# IR_Controller_v2.net
KiCad netlist of a schematic drawn in EAGLE
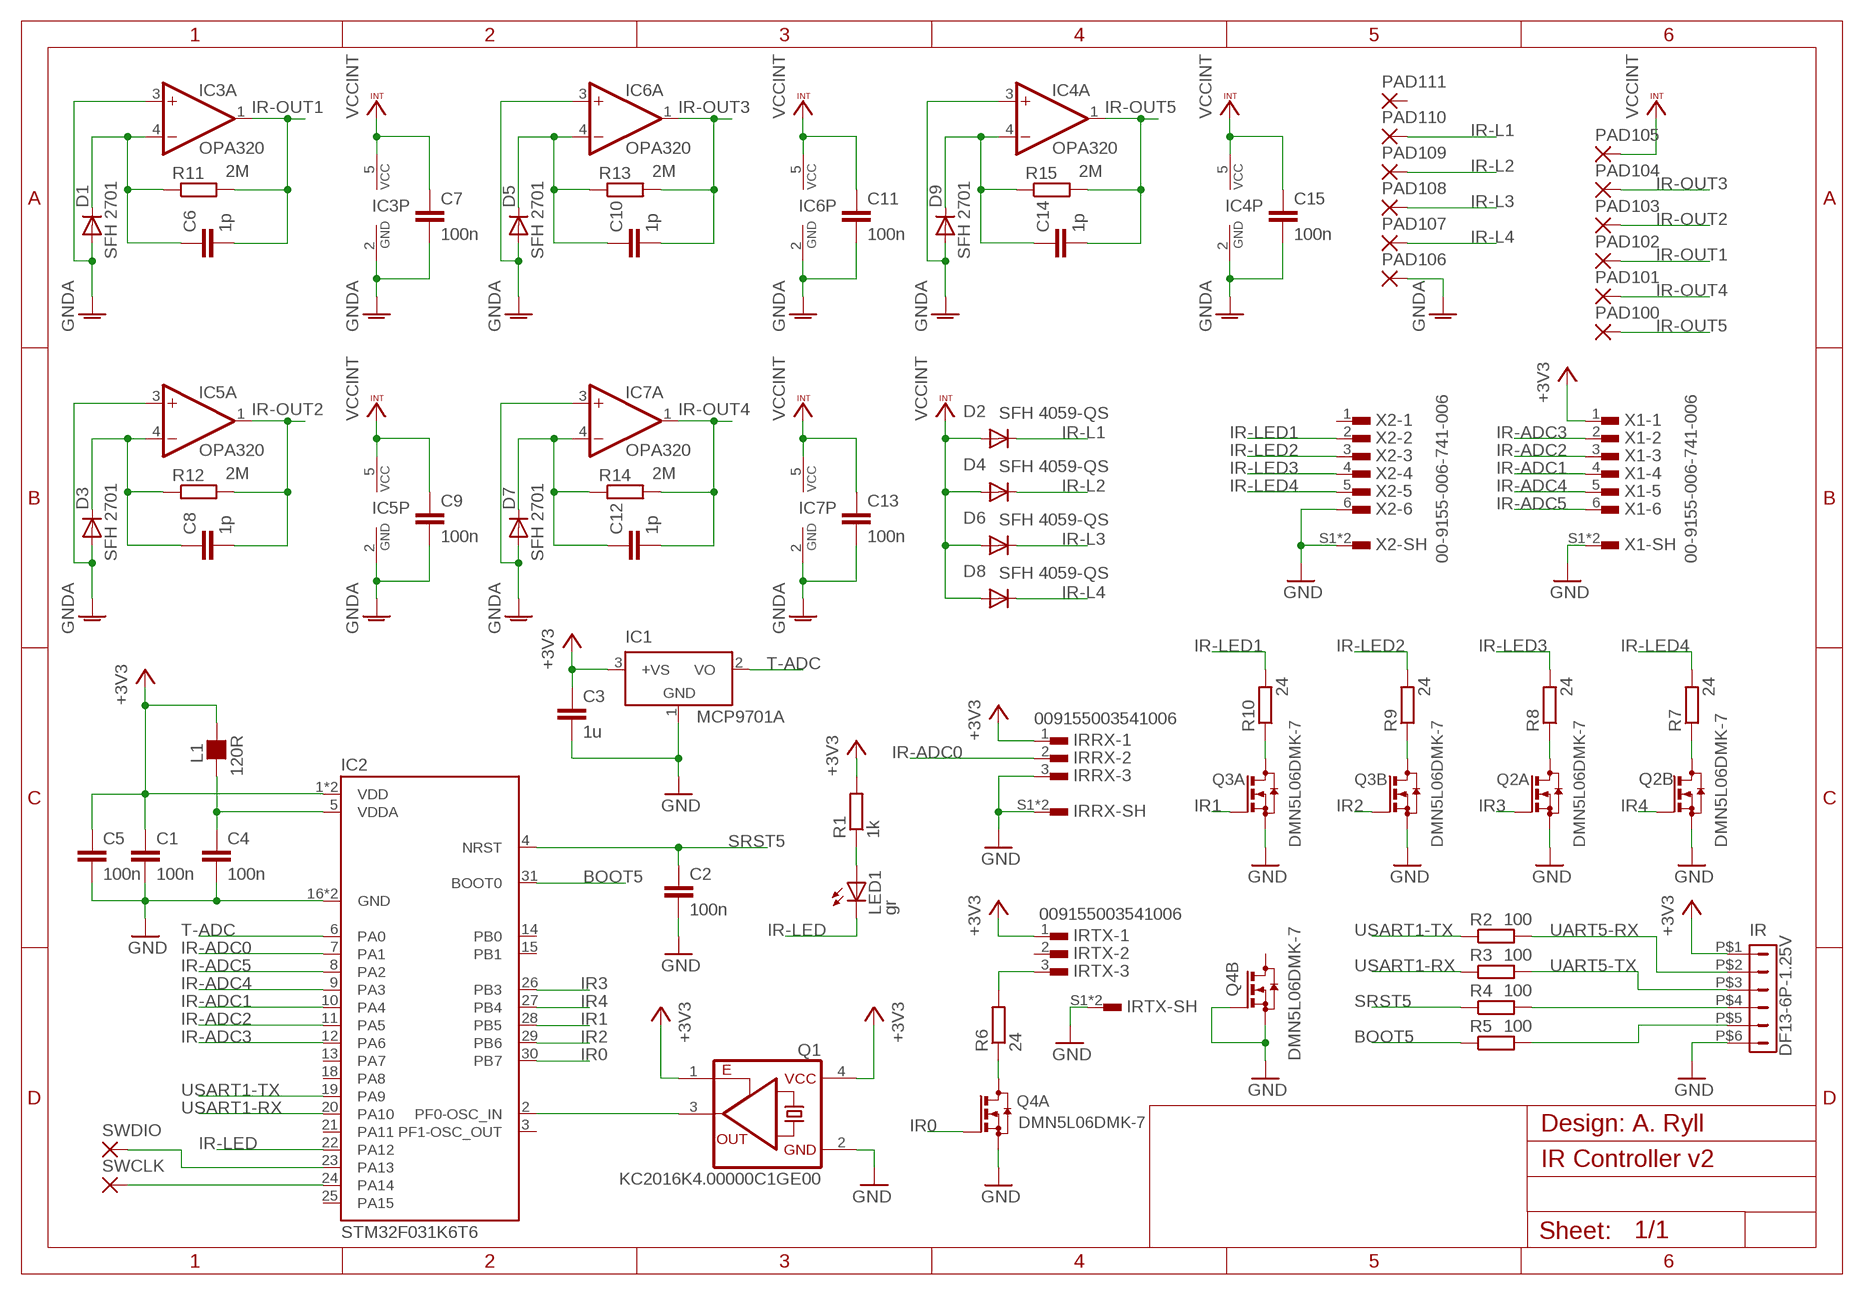
[diagram p0: schematic, sheet 1]

(export (version "E")
  (design (tool "Eeschema 10.0.6"))
  (components
    (comp (ref "C1")
      (value "100n")
      (footprint "eagle-import:C0603")
      (libsource (lib "eagle-import") (part "C-EUC0603"))
    )
    (comp (ref "C2")
      (value "100n")
      (footprint "eagle-import:C0603")
      (libsource (lib "eagle-import") (part "C-EUC0603"))
    )
    (comp (ref "C3")
      (value "1u")
      (footprint "eagle-import:C0603")
      (libsource (lib "eagle-import") (part "C-EUC0603"))
    )
    (comp (ref "C4")
      (value "100n")
      (footprint "eagle-import:C0603")
      (libsource (lib "eagle-import") (part "C-EUC0603"))
    )
    (comp (ref "C5")
      (value "100n")
      (footprint "eagle-import:C0603")
      (libsource (lib "eagle-import") (part "C-EUC0603"))
    )
    (comp (ref "C6")
      (value "1p")
      (footprint "eagle-import:C0603")
      (libsource (lib "eagle-import") (part "C-EUC0603"))
    )
    (comp (ref "C7")
      (value "100n")
      (footprint "eagle-import:C0603")
      (libsource (lib "eagle-import") (part "C-EUC0603"))
    )
    (comp (ref "C8")
      (value "1p")
      (footprint "eagle-import:C0603")
      (libsource (lib "eagle-import") (part "C-EUC0603"))
    )
    (comp (ref "C9")
      (value "100n")
      (footprint "eagle-import:C0603")
      (libsource (lib "eagle-import") (part "C-EUC0603"))
    )
    (comp (ref "C10")
      (value "1p")
      (footprint "eagle-import:C0603")
      (libsource (lib "eagle-import") (part "C-EUC0603"))
    )
    (comp (ref "C11")
      (value "100n")
      (footprint "eagle-import:C0603")
      (libsource (lib "eagle-import") (part "C-EUC0603"))
    )
    (comp (ref "C12")
      (value "1p")
      (footprint "eagle-import:C0603")
      (libsource (lib "eagle-import") (part "C-EUC0603"))
    )
    (comp (ref "C13")
      (value "100n")
      (footprint "eagle-import:C0603")
      (libsource (lib "eagle-import") (part "C-EUC0603"))
    )
    (comp (ref "C14")
      (value "1p")
      (footprint "eagle-import:C0603")
      (libsource (lib "eagle-import") (part "C-EUC0603"))
    )
    (comp (ref "C15")
      (value "100n")
      (footprint "eagle-import:C0603")
      (libsource (lib "eagle-import") (part "C-EUC0603"))
    )
    (comp (ref "D1")
      (value "SFH 2701")
      (footprint "eagle-import:LED-GULL")
      (libsource (lib "eagle-import") (part "DIODEG"))
    )
    (comp (ref "D2")
      (value "SFH 4059-QS")
      (footprint "eagle-import:LED-GULL")
      (libsource (lib "eagle-import") (part "DIODEG"))
    )
    (comp (ref "D3")
      (value "SFH 2701")
      (footprint "eagle-import:LED-GULL")
      (libsource (lib "eagle-import") (part "DIODEG"))
    )
    (comp (ref "D4")
      (value "SFH 4059-QS")
      (footprint "eagle-import:LED-GULL")
      (libsource (lib "eagle-import") (part "DIODEG"))
    )
    (comp (ref "D5")
      (value "SFH 2701")
      (footprint "eagle-import:LED-GULL")
      (libsource (lib "eagle-import") (part "DIODEG"))
    )
    (comp (ref "D6")
      (value "SFH 4059-QS")
      (footprint "eagle-import:LED-GULL")
      (libsource (lib "eagle-import") (part "DIODEG"))
    )
    (comp (ref "D7")
      (value "SFH 2701")
      (footprint "eagle-import:LED-GULL")
      (libsource (lib "eagle-import") (part "DIODEG"))
    )
    (comp (ref "D8")
      (value "SFH 4059-QS")
      (footprint "eagle-import:LED-GULL")
      (libsource (lib "eagle-import") (part "DIODEG"))
    )
    (comp (ref "D9")
      (value "SFH 2701")
      (footprint "eagle-import:LED-GULL")
      (libsource (lib "eagle-import") (part "DIODEG"))
    )
    (comp (ref "IC1")
      (value "MCP9701A")
      (footprint "eagle-import:TO92")
      (libsource (lib "eagle-import") (part "LM60P"))
    )
    (comp (ref "IC2")
      (value "STM32F031K6T6")
      (footprint "eagle-import:LQFP32-ST")
      (libsource (lib "eagle-import") (part "STM32F031K_TT"))
    )
    (comp (ref "IC3")
      (value "OPA320")
      (footprint "eagle-import:SOT23-5")
      (libsource (lib "eagle-import") (part "AD-OP1RT"))
    )
    (comp (ref "IC4")
      (value "OPA320")
      (footprint "eagle-import:SOT23-5")
      (libsource (lib "eagle-import") (part "AD-OP1RT"))
    )
    (comp (ref "IC5")
      (value "OPA320")
      (footprint "eagle-import:SOT23-5")
      (libsource (lib "eagle-import") (part "AD-OP1RT"))
    )
    (comp (ref "IC6")
      (value "OPA320")
      (footprint "eagle-import:SOT23-5")
      (libsource (lib "eagle-import") (part "AD-OP1RT"))
    )
    (comp (ref "IC7")
      (value "OPA320")
      (footprint "eagle-import:SOT23-5")
      (libsource (lib "eagle-import") (part "AD-OP1RT"))
    )
    (comp (ref "IR")
      (value "DF13-6P-1.25V")
      (footprint "eagle-import:DF13C-6P-1.25V")
      (libsource (lib "eagle-import") (part "DF13-6P-1.25V"))
    )
    (comp (ref "IRRX")
      (value "009155003541006")
      (footprint "eagle-import:AVX-CON3")
      (libsource (lib "eagle-import") (part "AVX-CON3"))
    )
    (comp (ref "IRTX")
      (value "009155003541006")
      (footprint "eagle-import:AVX-CON3")
      (libsource (lib "eagle-import") (part "AVX-CON3"))
    )
    (comp (ref "L1")
      (value "120R")
      (footprint "eagle-import:L0603")
      (libsource (lib "eagle-import") (part "FB_0603"))
    )
    (comp (ref "LED1")
      (value "gr")
      (footprint "eagle-import:CHIP-LED0603")
      (fields (field (name "SPICEPREFIX") "D"))
      (libsource (lib "eagle-import") (part "LEDCHIP-LED0603"))
    )
    (comp (ref "PAD100")
      (value "WIREPADSMD1,4-3")
      (footprint "eagle-import:SMD1,4-3")
      (libsource (lib "eagle-import") (part "WIREPADSMD1,4-3"))
    )
    (comp (ref "PAD101")
      (value "WIREPADSMD1,4-3")
      (footprint "eagle-import:SMD1,4-3")
      (libsource (lib "eagle-import") (part "WIREPADSMD1,4-3"))
    )
    (comp (ref "PAD102")
      (value "WIREPADSMD1,4-3")
      (footprint "eagle-import:SMD1,4-3")
      (libsource (lib "eagle-import") (part "WIREPADSMD1,4-3"))
    )
    (comp (ref "PAD103")
      (value "WIREPADSMD1,4-3")
      (footprint "eagle-import:SMD1,4-3")
      (libsource (lib "eagle-import") (part "WIREPADSMD1,4-3"))
    )
    (comp (ref "PAD104")
      (value "WIREPADSMD1,4-3")
      (footprint "eagle-import:SMD1,4-3")
      (libsource (lib "eagle-import") (part "WIREPADSMD1,4-3"))
    )
    (comp (ref "PAD105")
      (value "WIREPADSMD1,4-3")
      (footprint "eagle-import:SMD1,4-3")
      (libsource (lib "eagle-import") (part "WIREPADSMD1,4-3"))
    )
    (comp (ref "PAD106")
      (value "WIREPADSMD1,4-3")
      (footprint "eagle-import:SMD1,4-3")
      (libsource (lib "eagle-import") (part "WIREPADSMD1,4-3"))
    )
    (comp (ref "PAD107")
      (value "WIREPADSMD1,4-3")
      (footprint "eagle-import:SMD1,4-3")
      (libsource (lib "eagle-import") (part "WIREPADSMD1,4-3"))
    )
    (comp (ref "PAD108")
      (value "WIREPADSMD1,4-3")
      (footprint "eagle-import:SMD1,4-3")
      (libsource (lib "eagle-import") (part "WIREPADSMD1,4-3"))
    )
    (comp (ref "PAD109")
      (value "WIREPADSMD1,4-3")
      (footprint "eagle-import:SMD1,4-3")
      (libsource (lib "eagle-import") (part "WIREPADSMD1,4-3"))
    )
    (comp (ref "PAD110")
      (value "WIREPADSMD1,4-3")
      (footprint "eagle-import:SMD1,4-3")
      (libsource (lib "eagle-import") (part "WIREPADSMD1,4-3"))
    )
    (comp (ref "PAD111")
      (value "WIREPADSMD1,4-3")
      (footprint "eagle-import:SMD1,4-3")
      (libsource (lib "eagle-import") (part "WIREPADSMD1,4-3"))
    )
    (comp (ref "Q1")
      (value "KC2016K4.00000C1GE00")
      (footprint "eagle-import:OSCI-KC2016")
      (libsource (lib "eagle-import") (part "OSCIKC2016"))
    )
    (comp (ref "Q2")
      (value "DMN5L06DMK-7")
      (footprint "eagle-import:SOT26")
      (libsource (lib "eagle-import") (part "NMOS2"))
    )
    (comp (ref "Q3")
      (value "DMN5L06DMK-7")
      (footprint "eagle-import:SOT26")
      (libsource (lib "eagle-import") (part "NMOS2"))
    )
    (comp (ref "Q4")
      (value "DMN5L06DMK-7")
      (footprint "eagle-import:SOT26")
      (libsource (lib "eagle-import") (part "NMOS2"))
    )
    (comp (ref "R1")
      (value "1k")
      (footprint "eagle-import:R0603")
      (libsource (lib "eagle-import") (part "R-EU_R0603"))
    )
    (comp (ref "R2")
      (value "100")
      (footprint "eagle-import:R0805")
      (libsource (lib "eagle-import") (part "R-EU_R0805"))
    )
    (comp (ref "R3")
      (value "100")
      (footprint "eagle-import:R0805")
      (libsource (lib "eagle-import") (part "R-EU_R0805"))
    )
    (comp (ref "R4")
      (value "100")
      (footprint "eagle-import:R0805")
      (libsource (lib "eagle-import") (part "R-EU_R0805"))
    )
    (comp (ref "R5")
      (value "100")
      (footprint "eagle-import:R0805")
      (libsource (lib "eagle-import") (part "R-EU_R0805"))
    )
    (comp (ref "R6")
      (value "24")
      (footprint "eagle-import:R0805")
      (libsource (lib "eagle-import") (part "R-EU_R0805"))
    )
    (comp (ref "R7")
      (value "24")
      (footprint "eagle-import:R0805")
      (libsource (lib "eagle-import") (part "R-EU_R0805"))
    )
    (comp (ref "R8")
      (value "24")
      (footprint "eagle-import:R0805")
      (libsource (lib "eagle-import") (part "R-EU_R0805"))
    )
    (comp (ref "R9")
      (value "24")
      (footprint "eagle-import:R0805")
      (libsource (lib "eagle-import") (part "R-EU_R0805"))
    )
    (comp (ref "R10")
      (value "24")
      (footprint "eagle-import:R0805")
      (libsource (lib "eagle-import") (part "R-EU_R0805"))
    )
    (comp (ref "R11")
      (value "2M")
      (footprint "eagle-import:R0603")
      (libsource (lib "eagle-import") (part "R-EU_R0603"))
    )
    (comp (ref "R12")
      (value "2M")
      (footprint "eagle-import:R0603")
      (libsource (lib "eagle-import") (part "R-EU_R0603"))
    )
    (comp (ref "R13")
      (value "2M")
      (footprint "eagle-import:R0603")
      (libsource (lib "eagle-import") (part "R-EU_R0603"))
    )
    (comp (ref "R14")
      (value "2M")
      (footprint "eagle-import:R0603")
      (libsource (lib "eagle-import") (part "R-EU_R0603"))
    )
    (comp (ref "R15")
      (value "2M")
      (footprint "eagle-import:R0603")
      (libsource (lib "eagle-import") (part "R-EU_R0603"))
    )
    (comp (ref "SWCLK")
      (value "WIREPADSMD1,27-254")
      (footprint "eagle-import:SMD1,27-2,54")
      (libsource (lib "eagle-import") (part "WIREPADSMD1,27-254"))
    )
    (comp (ref "SWDIO")
      (value "WIREPADSMD1,27-254")
      (footprint "eagle-import:SMD1,27-2,54")
      (libsource (lib "eagle-import") (part "WIREPADSMD1,27-254"))
    )
    (comp (ref "X1")
      (value "00-9155-006-741-006")
      (footprint "eagle-import:AVX-CON6-2MM")
      (libsource (lib "eagle-import") (part "AVX-CON6"))
    )
    (comp (ref "X2")
      (value "00-9155-006-741-006")
      (footprint "eagle-import:AVX-CON6-2MM")
      (libsource (lib "eagle-import") (part "AVX-CON6"))
    )
  )
  (nets
    (net (code "1") (name "+3V3") (class "Default")
      (node (ref "C1") (pin "1") (pinfunction "1_1") (pintype "passive"))
      (node (ref "C3") (pin "1") (pinfunction "1_1") (pintype "passive"))
      (node (ref "C5") (pin "1") (pinfunction "1_1") (pintype "passive"))
      (node (ref "IC1") (pin "3") (pinfunction "+VS_3") (pintype "input"))
      (node (ref "IC2") (pin "1") (pinfunction "VDD_1") (pintype "bidirectional"))
      (node (ref "IC2") (pin "17") (pinfunction "VDD_17") (pintype "bidirectional"))
      (node (ref "IR") (pin "P$1") (pinfunction "1_P$1") (pintype "passive"))
      (node (ref "IRRX") (pin "1") (pinfunction "-1_1") (pintype "bidirectional"))
      (node (ref "IRTX") (pin "1") (pinfunction "-1_1") (pintype "bidirectional"))
      (node (ref "L1") (pin "2") (pinfunction "2_2") (pintype "passive"))
      (node (ref "Q1") (pin "1") (pinfunction "OE_1") (pintype "input"))
      (node (ref "Q1") (pin "4") (pinfunction "VCC_4") (pintype "power_in"))
      (node (ref "R1") (pin "2") (pinfunction "2_2") (pintype "passive"))
      (node (ref "X1") (pin "1") (pinfunction "-1_1") (pintype "bidirectional"))
    )
    (net (code "2") (name "/BOOT5") (class "Default")
      (node (ref "IC2") (pin "31") (pinfunction "BOOT0_31") (pintype "bidirectional"))
      (node (ref "R5") (pin "1") (pinfunction "1_1") (pintype "passive"))
    )
    (net (code "3") (name "/IR-ADC0") (class "Default")
      (node (ref "IC2") (pin "7") (pinfunction "PA1_7") (pintype "bidirectional"))
      (node (ref "IRRX") (pin "2") (pinfunction "-1_2") (pintype "bidirectional"))
    )
    (net (code "4") (name "/IR-ADC1") (class "Default")
      (node (ref "IC2") (pin "10") (pinfunction "PA4_10") (pintype "bidirectional"))
      (node (ref "X1") (pin "4") (pinfunction "-1_4") (pintype "bidirectional"))
    )
    (net (code "5") (name "/IR-ADC2") (class "Default")
      (node (ref "IC2") (pin "11") (pinfunction "PA5_11") (pintype "bidirectional"))
      (node (ref "X1") (pin "3") (pinfunction "-1_3") (pintype "bidirectional"))
    )
    (net (code "6") (name "/IR-ADC3") (class "Default")
      (node (ref "IC2") (pin "12") (pinfunction "PA6_12") (pintype "bidirectional"))
      (node (ref "X1") (pin "2") (pinfunction "-1_2") (pintype "bidirectional"))
    )
    (net (code "7") (name "/IR-ADC4") (class "Default")
      (node (ref "IC2") (pin "9") (pinfunction "PA3_9") (pintype "bidirectional"))
      (node (ref "X1") (pin "5") (pinfunction "-1_5") (pintype "bidirectional"))
    )
    (net (code "8") (name "/IR-ADC5") (class "Default")
      (node (ref "IC2") (pin "8") (pinfunction "PA2_8") (pintype "bidirectional"))
      (node (ref "X1") (pin "6") (pinfunction "-1_6") (pintype "bidirectional"))
    )
    (net (code "9") (name "/IR-L1") (class "Default")
      (node (ref "D2") (pin "C") (pinfunction "C_C") (pintype "passive"))
      (node (ref "PAD110") (pin "1") (pinfunction "P_1") (pintype "passive"))
    )
    (net (code "10") (name "/IR-L2") (class "Default")
      (node (ref "D4") (pin "C") (pinfunction "C_C") (pintype "passive"))
      (node (ref "PAD109") (pin "1") (pinfunction "P_1") (pintype "passive"))
    )
    (net (code "11") (name "/IR-L3") (class "Default")
      (node (ref "D6") (pin "C") (pinfunction "C_C") (pintype "passive"))
      (node (ref "PAD108") (pin "1") (pinfunction "P_1") (pintype "passive"))
    )
    (net (code "12") (name "/IR-L4") (class "Default")
      (node (ref "D8") (pin "C") (pinfunction "C_C") (pintype "passive"))
      (node (ref "PAD107") (pin "1") (pinfunction "P_1") (pintype "passive"))
    )
    (net (code "13") (name "/IR-LED") (class "Default")
      (node (ref "IC2") (pin "22") (pinfunction "PA12_22") (pintype "bidirectional"))
      (node (ref "LED1") (pin "C") (pinfunction "C_C") (pintype "passive"))
    )
    (net (code "14") (name "/IR-LED1") (class "Default")
      (node (ref "R10") (pin "2") (pinfunction "2_2") (pintype "passive"))
      (node (ref "X2") (pin "2") (pinfunction "-1_2") (pintype "bidirectional"))
    )
    (net (code "15") (name "/IR-LED2") (class "Default")
      (node (ref "R9") (pin "2") (pinfunction "2_2") (pintype "passive"))
      (node (ref "X2") (pin "3") (pinfunction "-1_3") (pintype "bidirectional"))
    )
    (net (code "16") (name "/IR-LED3") (class "Default")
      (node (ref "R8") (pin "2") (pinfunction "2_2") (pintype "passive"))
      (node (ref "X2") (pin "4") (pinfunction "-1_4") (pintype "bidirectional"))
    )
    (net (code "17") (name "/IR-LED4") (class "Default")
      (node (ref "R7") (pin "2") (pinfunction "2_2") (pintype "passive"))
      (node (ref "X2") (pin "5") (pinfunction "-1_5") (pintype "bidirectional"))
    )
    (net (code "18") (name "/IR-OUT1") (class "Default")
      (node (ref "C6") (pin "2") (pinfunction "2_2") (pintype "passive"))
      (node (ref "IC3") (pin "1") (pinfunction "OUT_1") (pintype "output"))
      (node (ref "PAD102") (pin "1") (pinfunction "P_1") (pintype "passive"))
      (node (ref "R11") (pin "2") (pinfunction "2_2") (pintype "passive"))
    )
    (net (code "19") (name "/IR-OUT2") (class "Default")
      (node (ref "C8") (pin "2") (pinfunction "2_2") (pintype "passive"))
      (node (ref "IC5") (pin "1") (pinfunction "OUT_1") (pintype "output"))
      (node (ref "PAD103") (pin "1") (pinfunction "P_1") (pintype "passive"))
      (node (ref "R12") (pin "2") (pinfunction "2_2") (pintype "passive"))
    )
    (net (code "20") (name "/IR-OUT3") (class "Default")
      (node (ref "C10") (pin "2") (pinfunction "2_2") (pintype "passive"))
      (node (ref "IC6") (pin "1") (pinfunction "OUT_1") (pintype "output"))
      (node (ref "PAD104") (pin "1") (pinfunction "P_1") (pintype "passive"))
      (node (ref "R13") (pin "2") (pinfunction "2_2") (pintype "passive"))
    )
    (net (code "21") (name "/IR-OUT4") (class "Default")
      (node (ref "C12") (pin "2") (pinfunction "2_2") (pintype "passive"))
      (node (ref "IC7") (pin "1") (pinfunction "OUT_1") (pintype "output"))
      (node (ref "PAD101") (pin "1") (pinfunction "P_1") (pintype "passive"))
      (node (ref "R14") (pin "2") (pinfunction "2_2") (pintype "passive"))
    )
    (net (code "22") (name "/IR-OUT5") (class "Default")
      (node (ref "C14") (pin "2") (pinfunction "2_2") (pintype "passive"))
      (node (ref "IC4") (pin "1") (pinfunction "OUT_1") (pintype "output"))
      (node (ref "PAD100") (pin "1") (pinfunction "P_1") (pintype "passive"))
      (node (ref "R15") (pin "2") (pinfunction "2_2") (pintype "passive"))
    )
    (net (code "23") (name "/IR0") (class "Default")
      (node (ref "IC2") (pin "30") (pinfunction "PB7_30") (pintype "bidirectional"))
      (node (ref "Q4") (pin "5") (pinfunction "G_5") (pintype "passive"))
    )
    (net (code "24") (name "/IR1") (class "Default")
      (node (ref "IC2") (pin "28") (pinfunction "PB5_28") (pintype "bidirectional"))
      (node (ref "Q3") (pin "5") (pinfunction "G_5") (pintype "passive"))
    )
    (net (code "25") (name "/IR2") (class "Default")
      (node (ref "IC2") (pin "29") (pinfunction "PB6_29") (pintype "bidirectional"))
      (node (ref "Q3") (pin "2") (pinfunction "G_2") (pintype "passive"))
    )
    (net (code "26") (name "/IR3") (class "Default")
      (node (ref "IC2") (pin "26") (pinfunction "PB3_26") (pintype "bidirectional"))
      (node (ref "Q2") (pin "5") (pinfunction "G_5") (pintype "passive"))
    )
    (net (code "27") (name "/IR4") (class "Default")
      (node (ref "IC2") (pin "27") (pinfunction "PB4_27") (pintype "bidirectional"))
      (node (ref "Q2") (pin "2") (pinfunction "G_2") (pintype "passive"))
    )
    (net (code "28") (name "/SRST5") (class "Default")
      (node (ref "C2") (pin "1") (pinfunction "1_1") (pintype "passive"))
      (node (ref "IC2") (pin "4") (pinfunction "NRST_4") (pintype "bidirectional"))
      (node (ref "R4") (pin "1") (pinfunction "1_1") (pintype "passive"))
    )
    (net (code "29") (name "/T-ADC") (class "Default")
      (node (ref "IC1") (pin "2") (pinfunction "VO_2") (pintype "input"))
      (node (ref "IC2") (pin "6") (pinfunction "PA0_6") (pintype "bidirectional"))
    )
    (net (code "30") (name "/UART5-RX") (class "Default")
      (node (ref "IR") (pin "P$2") (pinfunction "2_P$2") (pintype "passive"))
      (node (ref "R2") (pin "2") (pinfunction "2_2") (pintype "passive"))
    )
    (net (code "31") (name "/UART5-TX") (class "Default")
      (node (ref "IR") (pin "P$3") (pinfunction "3_P$3") (pintype "passive"))
      (node (ref "R3") (pin "2") (pinfunction "2_2") (pintype "passive"))
    )
    (net (code "32") (name "/USART1-RX") (class "Default")
      (node (ref "IC2") (pin "20") (pinfunction "PA10_20") (pintype "bidirectional"))
      (node (ref "R3") (pin "1") (pinfunction "1_1") (pintype "passive"))
    )
    (net (code "33") (name "/USART1-TX") (class "Default")
      (node (ref "IC2") (pin "19") (pinfunction "PA9_19") (pintype "bidirectional"))
      (node (ref "R2") (pin "1") (pinfunction "1_1") (pintype "passive"))
    )
    (net (code "34") (name "GND") (class "Default")
      (node (ref "C1") (pin "2") (pinfunction "2_2") (pintype "passive"))
      (node (ref "C2") (pin "2") (pinfunction "2_2") (pintype "passive"))
      (node (ref "C3") (pin "2") (pinfunction "2_2") (pintype "passive"))
      (node (ref "C4") (pin "2") (pinfunction "2_2") (pintype "passive"))
      (node (ref "C5") (pin "2") (pinfunction "2_2") (pintype "passive"))
      (node (ref "IC1") (pin "1") (pinfunction "GND_1") (pintype "power_in"))
      (node (ref "IC2") (pin "16") (pinfunction "GND_16") (pintype "bidirectional"))
      (node (ref "IC2") (pin "32") (pinfunction "GND_32") (pintype "bidirectional"))
      (node (ref "IR") (pin "P$6") (pinfunction "6_P$6") (pintype "passive"))
      (node (ref "IRRX") (pin "3") (pinfunction "-1_3") (pintype "bidirectional"))
      (node (ref "IRRX") (pin "S1") (pinfunction "-1_S1") (pintype "bidirectional"))
      (node (ref "IRRX") (pin "S2") (pinfunction "-1_S2") (pintype "bidirectional"))
      (node (ref "IRTX") (pin "S1") (pinfunction "-1_S1") (pintype "bidirectional"))
      (node (ref "IRTX") (pin "S2") (pinfunction "-1_S2") (pintype "bidirectional"))
      (node (ref "Q1") (pin "2") (pinfunction "GND_2") (pintype "power_in"))
      (node (ref "Q2") (pin "1") (pinfunction "S_1") (pintype "passive"))
      (node (ref "Q2") (pin "4") (pinfunction "S_4") (pintype "passive"))
      (node (ref "Q3") (pin "1") (pinfunction "S_1") (pintype "passive"))
      (node (ref "Q3") (pin "4") (pinfunction "S_4") (pintype "passive"))
      (node (ref "Q4") (pin "1") (pinfunction "S_1") (pintype "passive"))
      (node (ref "Q4") (pin "2") (pinfunction "G_2") (pintype "passive"))
      (node (ref "Q4") (pin "4") (pinfunction "S_4") (pintype "passive"))
      (node (ref "X1") (pin "S1") (pinfunction "-1_S1") (pintype "bidirectional"))
      (node (ref "X1") (pin "S2") (pinfunction "-1_S2") (pintype "bidirectional"))
      (node (ref "X2") (pin "6") (pinfunction "-1_6") (pintype "bidirectional"))
      (node (ref "X2") (pin "S1") (pinfunction "-1_S1") (pintype "bidirectional"))
      (node (ref "X2") (pin "S2") (pinfunction "-1_S2") (pintype "bidirectional"))
    )
    (net (code "35") (name "GNDA") (class "Default")
      (node (ref "C11") (pin "2") (pinfunction "2_2") (pintype "passive"))
      (node (ref "C13") (pin "2") (pinfunction "2_2") (pintype "passive"))
      (node (ref "C15") (pin "2") (pinfunction "2_2") (pintype "passive"))
      (node (ref "C7") (pin "2") (pinfunction "2_2") (pintype "passive"))
      (node (ref "C9") (pin "2") (pinfunction "2_2") (pintype "passive"))
      (node (ref "D1") (pin "A") (pinfunction "A_A") (pintype "passive"))
      (node (ref "D3") (pin "A") (pinfunction "A_A") (pintype "passive"))
      (node (ref "D5") (pin "A") (pinfunction "A_A") (pintype "passive"))
      (node (ref "D7") (pin "A") (pinfunction "A_A") (pintype "passive"))
      (node (ref "D9") (pin "A") (pinfunction "A_A") (pintype "passive"))
      (node (ref "IC3") (pin "2") (pinfunction "GND_2") (pintype "power_in"))
      (node (ref "IC3") (pin "3") (pinfunction "+IN_3") (pintype "input"))
      (node (ref "IC4") (pin "2") (pinfunction "GND_2") (pintype "power_in"))
      (node (ref "IC4") (pin "3") (pinfunction "+IN_3") (pintype "input"))
      (node (ref "IC5") (pin "2") (pinfunction "GND_2") (pintype "power_in"))
      (node (ref "IC5") (pin "3") (pinfunction "+IN_3") (pintype "input"))
      (node (ref "IC6") (pin "2") (pinfunction "GND_2") (pintype "power_in"))
      (node (ref "IC6") (pin "3") (pinfunction "+IN_3") (pintype "input"))
      (node (ref "IC7") (pin "2") (pinfunction "GND_2") (pintype "power_in"))
      (node (ref "IC7") (pin "3") (pinfunction "+IN_3") (pintype "input"))
      (node (ref "PAD106") (pin "1") (pinfunction "P_1") (pintype "passive"))
    )
    (net (code "36") (name "Net-(IC2-PA13)") (class "Default")
      (node (ref "IC2") (pin "23") (pinfunction "PA13_23") (pintype "bidirectional"))
      (node (ref "SWDIO") (pin "1") (pinfunction "P_1") (pintype "passive"))
    )
    (net (code "37") (name "Net-(IC2-PA14)") (class "Default")
      (node (ref "IC2") (pin "24") (pinfunction "PA14_24") (pintype "bidirectional"))
      (node (ref "SWCLK") (pin "1") (pinfunction "P_1") (pintype "passive"))
    )
    (net (code "38") (name "Net-(IC2-PF0-OSC_IN)") (class "Default")
      (node (ref "IC2") (pin "2") (pinfunction "PF0-OSC_IN_2") (pintype "bidirectional"))
      (node (ref "Q1") (pin "3") (pinfunction "FO_3") (pintype "output"))
    )
    (net (code "39") (name "Net-(IC2-VDDA)") (class "Default")
      (node (ref "C4") (pin "1") (pinfunction "1_1") (pintype "passive"))
      (node (ref "IC2") (pin "5") (pinfunction "VDDA_5") (pintype "bidirectional"))
      (node (ref "L1") (pin "1") (pinfunction "1_1") (pintype "passive"))
    )
    (net (code "40") (name "Net-(IC3A--IN)") (class "Default")
      (node (ref "C6") (pin "1") (pinfunction "1_1") (pintype "passive"))
      (node (ref "D1") (pin "C") (pinfunction "C_C") (pintype "passive"))
      (node (ref "IC3") (pin "4") (pinfunction "-IN_4") (pintype "input"))
      (node (ref "R11") (pin "1") (pinfunction "1_1") (pintype "passive"))
    )
    (net (code "41") (name "Net-(IC4A--IN)") (class "Default")
      (node (ref "C14") (pin "1") (pinfunction "1_1") (pintype "passive"))
      (node (ref "D9") (pin "C") (pinfunction "C_C") (pintype "passive"))
      (node (ref "IC4") (pin "4") (pinfunction "-IN_4") (pintype "input"))
      (node (ref "R15") (pin "1") (pinfunction "1_1") (pintype "passive"))
    )
    (net (code "42") (name "Net-(IC5A--IN)") (class "Default")
      (node (ref "C8") (pin "1") (pinfunction "1_1") (pintype "passive"))
      (node (ref "D3") (pin "C") (pinfunction "C_C") (pintype "passive"))
      (node (ref "IC5") (pin "4") (pinfunction "-IN_4") (pintype "input"))
      (node (ref "R12") (pin "1") (pinfunction "1_1") (pintype "passive"))
    )
    (net (code "43") (name "Net-(IC6A--IN)") (class "Default")
      (node (ref "C10") (pin "1") (pinfunction "1_1") (pintype "passive"))
      (node (ref "D5") (pin "C") (pinfunction "C_C") (pintype "passive"))
      (node (ref "IC6") (pin "4") (pinfunction "-IN_4") (pintype "input"))
      (node (ref "R13") (pin "1") (pinfunction "1_1") (pintype "passive"))
    )
    (net (code "44") (name "Net-(IC7A--IN)") (class "Default")
      (node (ref "C12") (pin "1") (pinfunction "1_1") (pintype "passive"))
      (node (ref "D7") (pin "C") (pinfunction "C_C") (pintype "passive"))
      (node (ref "IC7") (pin "4") (pinfunction "-IN_4") (pintype "input"))
      (node (ref "R14") (pin "1") (pinfunction "1_1") (pintype "passive"))
    )
    (net (code "45") (name "Net-(IR-4)") (class "Default")
      (node (ref "IR") (pin "P$4") (pinfunction "4_P$4") (pintype "passive"))
      (node (ref "R4") (pin "2") (pinfunction "2_2") (pintype "passive"))
    )
    (net (code "46") (name "Net-(IR-5)") (class "Default")
      (node (ref "IR") (pin "P$5") (pinfunction "5_P$5") (pintype "passive"))
      (node (ref "R5") (pin "2") (pinfunction "2_2") (pintype "passive"))
    )
    (net (code "47") (name "Net-(IRTXC--1)") (class "Default")
      (node (ref "IRTX") (pin "3") (pinfunction "-1_3") (pintype "bidirectional"))
      (node (ref "R6") (pin "2") (pinfunction "2_2") (pintype "passive"))
    )
    (net (code "48") (name "Net-(LED1-PadA)") (class "Default")
      (node (ref "LED1") (pin "A") (pinfunction "A_A") (pintype "passive"))
      (node (ref "R1") (pin "1") (pinfunction "1_1") (pintype "passive"))
    )
    (net (code "49") (name "Net-(Q2A-D)") (class "Default")
      (node (ref "Q2") (pin "3") (pinfunction "D_3") (pintype "passive"))
      (node (ref "R8") (pin "1") (pinfunction "1_1") (pintype "passive"))
    )
    (net (code "50") (name "Net-(Q2B-D)") (class "Default")
      (node (ref "Q2") (pin "6") (pinfunction "D_6") (pintype "passive"))
      (node (ref "R7") (pin "1") (pinfunction "1_1") (pintype "passive"))
    )
    (net (code "51") (name "Net-(Q3A-D)") (class "Default")
      (node (ref "Q3") (pin "3") (pinfunction "D_3") (pintype "passive"))
      (node (ref "R10") (pin "1") (pinfunction "1_1") (pintype "passive"))
    )
    (net (code "52") (name "Net-(Q3B-D)") (class "Default")
      (node (ref "Q3") (pin "6") (pinfunction "D_6") (pintype "passive"))
      (node (ref "R9") (pin "1") (pinfunction "1_1") (pintype "passive"))
    )
    (net (code "53") (name "Net-(Q4A-D)") (class "Default")
      (node (ref "Q4") (pin "3") (pinfunction "D_3") (pintype "passive"))
      (node (ref "R6") (pin "1") (pinfunction "1_1") (pintype "passive"))
    )
    (net (code "54") (name "VCCINT") (class "Default")
      (node (ref "C11") (pin "1") (pinfunction "1_1") (pintype "passive"))
      (node (ref "C13") (pin "1") (pinfunction "1_1") (pintype "passive"))
      (node (ref "C15") (pin "1") (pinfunction "1_1") (pintype "passive"))
      (node (ref "C7") (pin "1") (pinfunction "1_1") (pintype "passive"))
      (node (ref "C9") (pin "1") (pinfunction "1_1") (pintype "passive"))
      (node (ref "D2") (pin "A") (pinfunction "A_A") (pintype "passive"))
      (node (ref "D4") (pin "A") (pinfunction "A_A") (pintype "passive"))
      (node (ref "D6") (pin "A") (pinfunction "A_A") (pintype "passive"))
      (node (ref "D8") (pin "A") (pinfunction "A_A") (pintype "passive"))
      (node (ref "IC3") (pin "5") (pinfunction "VCC_5") (pintype "power_in"))
      (node (ref "IC4") (pin "5") (pinfunction "VCC_5") (pintype "power_in"))
      (node (ref "IC5") (pin "5") (pinfunction "VCC_5") (pintype "power_in"))
      (node (ref "IC6") (pin "5") (pinfunction "VCC_5") (pintype "power_in"))
      (node (ref "IC7") (pin "5") (pinfunction "VCC_5") (pintype "power_in"))
      (node (ref "PAD105") (pin "1") (pinfunction "P_1") (pintype "passive"))
    )
    (net (code "55") (name "unconnected-(IC2-PA7-Pad13)") (class "Default")
      (node (ref "IC2") (pin "13") (pinfunction "PA7_13") (pintype "bidirectional"))
    )
    (net (code "56") (name "unconnected-(IC2-PA8-Pad18)") (class "Default")
      (node (ref "IC2") (pin "18") (pinfunction "PA8_18") (pintype "bidirectional"))
    )
    (net (code "57") (name "unconnected-(IC2-PA11-Pad21)") (class "Default")
      (node (ref "IC2") (pin "21") (pinfunction "PA11_21") (pintype "bidirectional"))
    )
    (net (code "58") (name "unconnected-(IC2-PA15-Pad25)") (class "Default")
      (node (ref "IC2") (pin "25") (pinfunction "PA15_25") (pintype "bidirectional"))
    )
    (net (code "59") (name "unconnected-(IC2-PB0-Pad14)") (class "Default")
      (node (ref "IC2") (pin "14") (pinfunction "PB0_14") (pintype "bidirectional"))
    )
    (net (code "60") (name "unconnected-(IC2-PB1-Pad15)") (class "Default")
      (node (ref "IC2") (pin "15") (pinfunction "PB1_15") (pintype "bidirectional"))
    )
    (net (code "61") (name "unconnected-(IC2-PF1-OSC_OUT-Pad3)") (class "Default")
      (node (ref "IC2") (pin "3") (pinfunction "PF1-OSC_OUT_3") (pintype "bidirectional"))
    )
    (net (code "62") (name "unconnected-(IRTXB--1-Pad2)") (class "Default")
      (node (ref "IRTX") (pin "2") (pinfunction "-1_2") (pintype "bidirectional"))
    )
    (net (code "63") (name "unconnected-(PAD111-P-Pad1)") (class "Default")
      (node (ref "PAD111") (pin "1") (pinfunction "P_1") (pintype "passive"))
    )
    (net (code "64") (name "unconnected-(Q4B-D-Pad6)") (class "Default")
      (node (ref "Q4") (pin "6") (pinfunction "D_6") (pintype "passive"))
    )
    (net (code "65") (name "unconnected-(X2A--1-Pad1)") (class "Default")
      (node (ref "X2") (pin "1") (pinfunction "-1_1") (pintype "bidirectional"))
    )
  )
)
